# AccessPanelV3.net
KiCad netlist of a schematic drawn in EAGLE
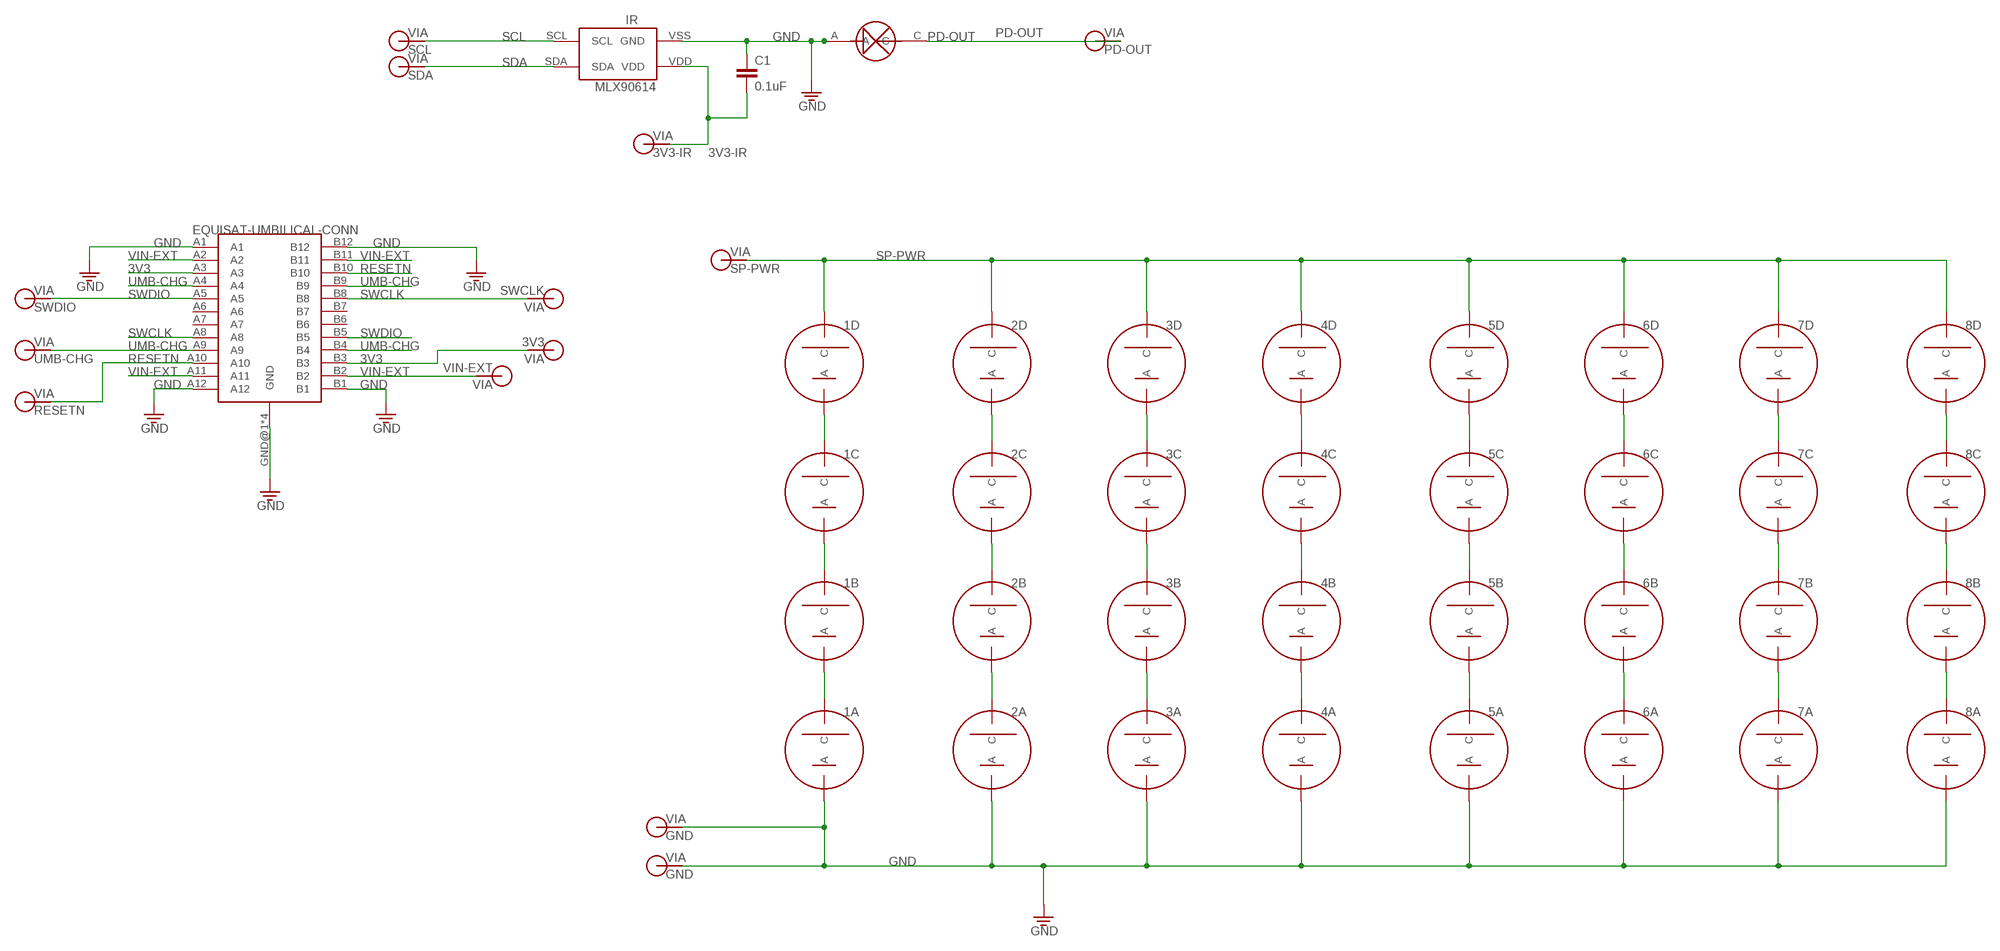
[diagram p0: schematic, sheet 1]

(export (version "E")
  (design (tool "Eeschema 10.0.6"))
  (components
    (comp (ref "1A")
      (value "SOLARCELLV3")
      (footprint "eagle-import:TRISOLX-V3")
      (libsource (lib "eagle-import") (part "SOLARCELLV3"))
    )
    (comp (ref "1B")
      (value "SOLARCELLV3")
      (footprint "eagle-import:TRISOLX-V3")
      (libsource (lib "eagle-import") (part "SOLARCELLV3"))
    )
    (comp (ref "1C")
      (value "SOLARCELLV3")
      (footprint "eagle-import:TRISOLX-V3")
      (libsource (lib "eagle-import") (part "SOLARCELLV3"))
    )
    (comp (ref "1D")
      (value "SOLARCELLV3")
      (footprint "eagle-import:TRISOLX-V3")
      (libsource (lib "eagle-import") (part "SOLARCELLV3"))
    )
    (comp (ref "2A")
      (value "SOLARCELLV3")
      (footprint "eagle-import:TRISOLX-V3")
      (libsource (lib "eagle-import") (part "SOLARCELLV3"))
    )
    (comp (ref "2B")
      (value "SOLARCELLV3")
      (footprint "eagle-import:TRISOLX-V3")
      (libsource (lib "eagle-import") (part "SOLARCELLV3"))
    )
    (comp (ref "2C")
      (value "SOLARCELLV3")
      (footprint "eagle-import:TRISOLX-V3")
      (libsource (lib "eagle-import") (part "SOLARCELLV3"))
    )
    (comp (ref "2D")
      (value "SOLARCELLV3")
      (footprint "eagle-import:TRISOLX-V3")
      (libsource (lib "eagle-import") (part "SOLARCELLV3"))
    )
    (comp (ref "3A")
      (value "SOLARCELLV3")
      (footprint "eagle-import:TRISOLX-V3")
      (libsource (lib "eagle-import") (part "SOLARCELLV3"))
    )
    (comp (ref "3B")
      (value "SOLARCELLV3")
      (footprint "eagle-import:TRISOLX-V3")
      (libsource (lib "eagle-import") (part "SOLARCELLV3"))
    )
    (comp (ref "3C")
      (value "SOLARCELLV3")
      (footprint "eagle-import:TRISOLX-V3")
      (libsource (lib "eagle-import") (part "SOLARCELLV3"))
    )
    (comp (ref "3D")
      (value "SOLARCELLV3")
      (footprint "eagle-import:TRISOLX-V3")
      (libsource (lib "eagle-import") (part "SOLARCELLV3"))
    )
    (comp (ref "4A")
      (value "SOLARCELLV3")
      (footprint "eagle-import:TRISOLX-V3")
      (libsource (lib "eagle-import") (part "SOLARCELLV3"))
    )
    (comp (ref "4B")
      (value "SOLARCELLV3")
      (footprint "eagle-import:TRISOLX-V3")
      (libsource (lib "eagle-import") (part "SOLARCELLV3"))
    )
    (comp (ref "4C")
      (value "SOLARCELLV3")
      (footprint "eagle-import:TRISOLX-V3")
      (libsource (lib "eagle-import") (part "SOLARCELLV3"))
    )
    (comp (ref "4D")
      (value "SOLARCELLV3")
      (footprint "eagle-import:TRISOLX-V3")
      (libsource (lib "eagle-import") (part "SOLARCELLV3"))
    )
    (comp (ref "5A")
      (value "SOLARCELLV3")
      (footprint "eagle-import:TRISOLX-V3")
      (libsource (lib "eagle-import") (part "SOLARCELLV3"))
    )
    (comp (ref "5B")
      (value "SOLARCELLV3")
      (footprint "eagle-import:TRISOLX-V3")
      (libsource (lib "eagle-import") (part "SOLARCELLV3"))
    )
    (comp (ref "5C")
      (value "SOLARCELLV3")
      (footprint "eagle-import:TRISOLX-V3")
      (libsource (lib "eagle-import") (part "SOLARCELLV3"))
    )
    (comp (ref "5D")
      (value "SOLARCELLV3")
      (footprint "eagle-import:TRISOLX-V3")
      (libsource (lib "eagle-import") (part "SOLARCELLV3"))
    )
    (comp (ref "6A")
      (value "SOLARCELLV3")
      (footprint "eagle-import:TRISOLX-V3")
      (libsource (lib "eagle-import") (part "SOLARCELLV3"))
    )
    (comp (ref "6B")
      (value "SOLARCELLV3")
      (footprint "eagle-import:TRISOLX-V3")
      (libsource (lib "eagle-import") (part "SOLARCELLV3"))
    )
    (comp (ref "6C")
      (value "SOLARCELLV3")
      (footprint "eagle-import:TRISOLX-V3")
      (libsource (lib "eagle-import") (part "SOLARCELLV3"))
    )
    (comp (ref "6D")
      (value "SOLARCELLV3")
      (footprint "eagle-import:TRISOLX-V3")
      (libsource (lib "eagle-import") (part "SOLARCELLV3"))
    )
    (comp (ref "7A")
      (value "SOLARCELLV3")
      (footprint "eagle-import:TRISOLX-V3")
      (libsource (lib "eagle-import") (part "SOLARCELLV3"))
    )
    (comp (ref "7B")
      (value "SOLARCELLV3")
      (footprint "eagle-import:TRISOLX-V3")
      (libsource (lib "eagle-import") (part "SOLARCELLV3"))
    )
    (comp (ref "7C")
      (value "SOLARCELLV3")
      (footprint "eagle-import:TRISOLX-V3")
      (libsource (lib "eagle-import") (part "SOLARCELLV3"))
    )
    (comp (ref "7D")
      (value "SOLARCELLV3")
      (footprint "eagle-import:TRISOLX-V3")
      (libsource (lib "eagle-import") (part "SOLARCELLV3"))
    )
    (comp (ref "8A")
      (value "SOLARCELLV3")
      (footprint "eagle-import:TRISOLX-V3")
      (libsource (lib "eagle-import") (part "SOLARCELLV3"))
    )
    (comp (ref "8B")
      (value "SOLARCELLV3")
      (footprint "eagle-import:TRISOLX-V3")
      (libsource (lib "eagle-import") (part "SOLARCELLV3"))
    )
    (comp (ref "8C")
      (value "SOLARCELLV3")
      (footprint "eagle-import:TRISOLX-V3")
      (libsource (lib "eagle-import") (part "SOLARCELLV3"))
    )
    (comp (ref "8D")
      (value "SOLARCELLV3")
      (footprint "eagle-import:TRISOLX-V3")
      (libsource (lib "eagle-import") (part "SOLARCELLV3"))
    )
    (comp (ref "C1")
      (value "0.1uF")
      (footprint "eagle-import:0805")
      (libsource (lib "eagle-import") (part "CAP0805"))
    )
    (comp (ref "IR")
      (value "MXL90614")
      (footprint "eagle-import:MXL90620")
      (libsource (lib "eagle-import") (part "MXL90614"))
    )
    (comp (ref "PD")
      (value "TEMD6200")
      (footprint "eagle-import:TEMD6200")
      (libsource (lib "eagle-import") (part "TEMD6200"))
    )
    (comp (ref "SCL")
      (value "SCL")
      (footprint "eagle-import:VIA-60MIL")
      (libsource (lib "eagle-import") (part "VIA-60MIL"))
    )
    (comp (ref "SDA")
      (value "SDA")
      (footprint "eagle-import:VIA-60MIL")
      (libsource (lib "eagle-import") (part "VIA-60MIL"))
    )
    (comp (ref "UMB-CONN")
      (value "EQUISAT-UMBILICAL-CONN")
      (footprint "eagle-import:USB-C-RCPT-SMT")
      (libsource (lib "eagle-import") (part "EQUISAT-UMBILICAL-CONN"))
    )
    (comp (ref "V1")
      (value "SP-PWR")
      (footprint "eagle-import:VIA-60MIL")
      (libsource (lib "eagle-import") (part "VIA-60MIL"))
    )
    (comp (ref "V2")
      (value "GND")
      (footprint "eagle-import:VIA-60MIL")
      (libsource (lib "eagle-import") (part "VIA-60MIL"))
    )
    (comp (ref "V3")
      (value "3V3-IR")
      (footprint "eagle-import:VIA-60MIL")
      (libsource (lib "eagle-import") (part "VIA-60MIL"))
    )
    (comp (ref "V4")
      (value "GND")
      (footprint "eagle-import:VIA-60MIL")
      (libsource (lib "eagle-import") (part "VIA-60MIL"))
    )
    (comp (ref "V5")
      (value "UMB-CHG")
      (footprint "eagle-import:VIA-60MIL")
      (libsource (lib "eagle-import") (part "VIA-60MIL"))
    )
    (comp (ref "V6")
      (value "PD-OUT")
      (footprint "eagle-import:VIA-60MIL")
      (libsource (lib "eagle-import") (part "VIA-60MIL"))
    )
    (comp (ref "V7")
      (value "VIN-EXT")
      (footprint "eagle-import:VIA-60MIL")
      (libsource (lib "eagle-import") (part "VIA-60MIL"))
    )
    (comp (ref "V8")
      (value "RESETN")
      (footprint "eagle-import:VIA-60MIL")
      (libsource (lib "eagle-import") (part "VIA-60MIL"))
    )
    (comp (ref "V9")
      (value "3V3")
      (footprint "eagle-import:VIA-60MIL")
      (libsource (lib "eagle-import") (part "VIA-60MIL"))
    )
    (comp (ref "V10")
      (value "SWCLK")
      (footprint "eagle-import:VIA-60MIL")
      (libsource (lib "eagle-import") (part "VIA-60MIL"))
    )
    (comp (ref "V11")
      (value "SWDIO")
      (footprint "eagle-import:VIA-60MIL")
      (libsource (lib "eagle-import") (part "VIA-60MIL"))
    )
  )
  (nets
    (net (code "1") (name "/3V3") (class "Default")
      (node (ref "UMB-CONN") (pin "A3") (pinfunction "A3_A3") (pintype "bidirectional"))
      (node (ref "UMB-CONN") (pin "B3") (pinfunction "B3_B3") (pintype "bidirectional"))
      (node (ref "V9") (pin "P$1") (pinfunction "P$1_P$1") (pintype "bidirectional"))
    )
    (net (code "2") (name "/3V3-IR") (class "Default")
      (node (ref "C1") (pin "2") (pinfunction "2_2") (pintype "passive"))
      (node (ref "IR") (pin "VDD") (pinfunction "VDD_VDD") (pintype "bidirectional"))
      (node (ref "V3") (pin "P$1") (pinfunction "P$1_P$1") (pintype "bidirectional"))
    )
    (net (code "3") (name "/PD-OUT") (class "Default")
      (node (ref "PD") (pin "C") (pinfunction "C_C") (pintype "bidirectional"))
      (node (ref "V6") (pin "P$1") (pinfunction "P$1_P$1") (pintype "bidirectional"))
    )
    (net (code "4") (name "/RESETN") (class "Default")
      (node (ref "UMB-CONN") (pin "A10") (pinfunction "A10_A10") (pintype "bidirectional"))
      (node (ref "UMB-CONN") (pin "B10") (pinfunction "B10_B10") (pintype "bidirectional"))
      (node (ref "V8") (pin "P$1") (pinfunction "P$1_P$1") (pintype "bidirectional"))
    )
    (net (code "5") (name "/SCL") (class "Default")
      (node (ref "IR") (pin "SCL") (pinfunction "SCL_SCL") (pintype "bidirectional"))
      (node (ref "SCL") (pin "P$1") (pinfunction "P$1_P$1") (pintype "bidirectional"))
    )
    (net (code "6") (name "/SDA") (class "Default")
      (node (ref "IR") (pin "SDA") (pinfunction "SDA_SDA") (pintype "bidirectional"))
      (node (ref "SDA") (pin "P$1") (pinfunction "P$1_P$1") (pintype "bidirectional"))
    )
    (net (code "7") (name "/SP-PWR") (class "Default")
      (node (ref "1D") (pin "CATHODE") (pinfunction "C_CATHODE") (pintype "bidirectional"))
      (node (ref "2D") (pin "CATHODE") (pinfunction "C_CATHODE") (pintype "bidirectional"))
      (node (ref "3D") (pin "CATHODE") (pinfunction "C_CATHODE") (pintype "bidirectional"))
      (node (ref "4D") (pin "CATHODE") (pinfunction "C_CATHODE") (pintype "bidirectional"))
      (node (ref "5D") (pin "CATHODE") (pinfunction "C_CATHODE") (pintype "bidirectional"))
      (node (ref "6D") (pin "CATHODE") (pinfunction "C_CATHODE") (pintype "bidirectional"))
      (node (ref "7D") (pin "CATHODE") (pinfunction "C_CATHODE") (pintype "bidirectional"))
      (node (ref "8D") (pin "CATHODE") (pinfunction "C_CATHODE") (pintype "bidirectional"))
      (node (ref "V1") (pin "P$1") (pinfunction "P$1_P$1") (pintype "bidirectional"))
    )
    (net (code "8") (name "/SWCLK") (class "Default")
      (node (ref "UMB-CONN") (pin "A8") (pinfunction "A8_A8") (pintype "bidirectional"))
      (node (ref "UMB-CONN") (pin "B8") (pinfunction "B8_B8") (pintype "bidirectional"))
      (node (ref "V10") (pin "P$1") (pinfunction "P$1_P$1") (pintype "bidirectional"))
    )
    (net (code "9") (name "/SWDIO") (class "Default")
      (node (ref "UMB-CONN") (pin "A5") (pinfunction "A5_A5") (pintype "bidirectional"))
      (node (ref "UMB-CONN") (pin "B5") (pinfunction "B5_B5") (pintype "bidirectional"))
      (node (ref "V11") (pin "P$1") (pinfunction "P$1_P$1") (pintype "bidirectional"))
    )
    (net (code "10") (name "/UMB-CHG") (class "Default")
      (node (ref "UMB-CONN") (pin "A4") (pinfunction "A4_A4") (pintype "bidirectional"))
      (node (ref "UMB-CONN") (pin "A9") (pinfunction "A9_A9") (pintype "bidirectional"))
      (node (ref "UMB-CONN") (pin "B4") (pinfunction "B4_B4") (pintype "bidirectional"))
      (node (ref "UMB-CONN") (pin "B9") (pinfunction "B9_B9") (pintype "bidirectional"))
      (node (ref "V5") (pin "P$1") (pinfunction "P$1_P$1") (pintype "bidirectional"))
    )
    (net (code "11") (name "/VIN-EXT") (class "Default")
      (node (ref "UMB-CONN") (pin "A11") (pinfunction "A11_A11") (pintype "bidirectional"))
      (node (ref "UMB-CONN") (pin "A2") (pinfunction "A2_A2") (pintype "bidirectional"))
      (node (ref "UMB-CONN") (pin "B11") (pinfunction "B11_B11") (pintype "bidirectional"))
      (node (ref "UMB-CONN") (pin "B2") (pinfunction "B2_B2") (pintype "bidirectional"))
      (node (ref "V7") (pin "P$1") (pinfunction "P$1_P$1") (pintype "bidirectional"))
    )
    (net (code "12") (name "GND") (class "Default")
      (node (ref "1A") (pin "ANODE") (pinfunction "A_ANODE") (pintype "bidirectional"))
      (node (ref "2A") (pin "ANODE") (pinfunction "A_ANODE") (pintype "bidirectional"))
      (node (ref "3A") (pin "ANODE") (pinfunction "A_ANODE") (pintype "bidirectional"))
      (node (ref "4A") (pin "ANODE") (pinfunction "A_ANODE") (pintype "bidirectional"))
      (node (ref "5A") (pin "ANODE") (pinfunction "A_ANODE") (pintype "bidirectional"))
      (node (ref "6A") (pin "ANODE") (pinfunction "A_ANODE") (pintype "bidirectional"))
      (node (ref "7A") (pin "ANODE") (pinfunction "A_ANODE") (pintype "bidirectional"))
      (node (ref "8A") (pin "ANODE") (pinfunction "A_ANODE") (pintype "bidirectional"))
      (node (ref "C1") (pin "1") (pinfunction "1_1") (pintype "passive"))
      (node (ref "IR") (pin "VSS") (pinfunction "GND_VSS") (pintype "bidirectional"))
      (node (ref "PD") (pin "A") (pinfunction "A_A") (pintype "bidirectional"))
      (node (ref "UMB-CONN") (pin "A1") (pinfunction "A1_A1") (pintype "bidirectional"))
      (node (ref "UMB-CONN") (pin "A12") (pinfunction "A12_A12") (pintype "bidirectional"))
      (node (ref "UMB-CONN") (pin "B1") (pinfunction "B1_B1") (pintype "bidirectional"))
      (node (ref "UMB-CONN") (pin "B12") (pinfunction "B12_B12") (pintype "bidirectional"))
      (node (ref "UMB-CONN") (pin "GND@1") (pinfunction "GND_GND@1") (pintype "bidirectional"))
      (node (ref "UMB-CONN") (pin "GND@2") (pinfunction "GND_GND@2") (pintype "bidirectional"))
      (node (ref "UMB-CONN") (pin "GND@3") (pinfunction "GND_GND@3") (pintype "bidirectional"))
      (node (ref "UMB-CONN") (pin "GND@4") (pinfunction "GND_GND@4") (pintype "bidirectional"))
      (node (ref "V2") (pin "P$1") (pinfunction "P$1_P$1") (pintype "bidirectional"))
      (node (ref "V4") (pin "P$1") (pinfunction "P$1_P$1") (pintype "bidirectional"))
    )
    (net (code "13") (name "Net-(1A-C)") (class "Default")
      (node (ref "1A") (pin "CATHODE") (pinfunction "C_CATHODE") (pintype "bidirectional"))
      (node (ref "1B") (pin "ANODE") (pinfunction "A_ANODE") (pintype "bidirectional"))
    )
    (net (code "14") (name "Net-(1B-C)") (class "Default")
      (node (ref "1B") (pin "CATHODE") (pinfunction "C_CATHODE") (pintype "bidirectional"))
      (node (ref "1C") (pin "ANODE") (pinfunction "A_ANODE") (pintype "bidirectional"))
    )
    (net (code "15") (name "Net-(1C-C)") (class "Default")
      (node (ref "1C") (pin "CATHODE") (pinfunction "C_CATHODE") (pintype "bidirectional"))
      (node (ref "1D") (pin "ANODE") (pinfunction "A_ANODE") (pintype "bidirectional"))
    )
    (net (code "16") (name "Net-(2A-C)") (class "Default")
      (node (ref "2A") (pin "CATHODE") (pinfunction "C_CATHODE") (pintype "bidirectional"))
      (node (ref "2B") (pin "ANODE") (pinfunction "A_ANODE") (pintype "bidirectional"))
    )
    (net (code "17") (name "Net-(2B-C)") (class "Default")
      (node (ref "2B") (pin "CATHODE") (pinfunction "C_CATHODE") (pintype "bidirectional"))
      (node (ref "2C") (pin "ANODE") (pinfunction "A_ANODE") (pintype "bidirectional"))
    )
    (net (code "18") (name "Net-(2C-C)") (class "Default")
      (node (ref "2C") (pin "CATHODE") (pinfunction "C_CATHODE") (pintype "bidirectional"))
      (node (ref "2D") (pin "ANODE") (pinfunction "A_ANODE") (pintype "bidirectional"))
    )
    (net (code "19") (name "Net-(3A-C)") (class "Default")
      (node (ref "3A") (pin "CATHODE") (pinfunction "C_CATHODE") (pintype "bidirectional"))
      (node (ref "3B") (pin "ANODE") (pinfunction "A_ANODE") (pintype "bidirectional"))
    )
    (net (code "20") (name "Net-(3B-C)") (class "Default")
      (node (ref "3B") (pin "CATHODE") (pinfunction "C_CATHODE") (pintype "bidirectional"))
      (node (ref "3C") (pin "ANODE") (pinfunction "A_ANODE") (pintype "bidirectional"))
    )
    (net (code "21") (name "Net-(3C-C)") (class "Default")
      (node (ref "3C") (pin "CATHODE") (pinfunction "C_CATHODE") (pintype "bidirectional"))
      (node (ref "3D") (pin "ANODE") (pinfunction "A_ANODE") (pintype "bidirectional"))
    )
    (net (code "22") (name "Net-(4A-C)") (class "Default")
      (node (ref "4A") (pin "CATHODE") (pinfunction "C_CATHODE") (pintype "bidirectional"))
      (node (ref "4B") (pin "ANODE") (pinfunction "A_ANODE") (pintype "bidirectional"))
    )
    (net (code "23") (name "Net-(4B-C)") (class "Default")
      (node (ref "4B") (pin "CATHODE") (pinfunction "C_CATHODE") (pintype "bidirectional"))
      (node (ref "4C") (pin "ANODE") (pinfunction "A_ANODE") (pintype "bidirectional"))
    )
    (net (code "24") (name "Net-(4C-C)") (class "Default")
      (node (ref "4C") (pin "CATHODE") (pinfunction "C_CATHODE") (pintype "bidirectional"))
      (node (ref "4D") (pin "ANODE") (pinfunction "A_ANODE") (pintype "bidirectional"))
    )
    (net (code "25") (name "Net-(5A-C)") (class "Default")
      (node (ref "5A") (pin "CATHODE") (pinfunction "C_CATHODE") (pintype "bidirectional"))
      (node (ref "5B") (pin "ANODE") (pinfunction "A_ANODE") (pintype "bidirectional"))
    )
    (net (code "26") (name "Net-(5B-C)") (class "Default")
      (node (ref "5B") (pin "CATHODE") (pinfunction "C_CATHODE") (pintype "bidirectional"))
      (node (ref "5C") (pin "ANODE") (pinfunction "A_ANODE") (pintype "bidirectional"))
    )
    (net (code "27") (name "Net-(5C-C)") (class "Default")
      (node (ref "5C") (pin "CATHODE") (pinfunction "C_CATHODE") (pintype "bidirectional"))
      (node (ref "5D") (pin "ANODE") (pinfunction "A_ANODE") (pintype "bidirectional"))
    )
    (net (code "28") (name "Net-(6A-C)") (class "Default")
      (node (ref "6A") (pin "CATHODE") (pinfunction "C_CATHODE") (pintype "bidirectional"))
      (node (ref "6B") (pin "ANODE") (pinfunction "A_ANODE") (pintype "bidirectional"))
    )
    (net (code "29") (name "Net-(6B-C)") (class "Default")
      (node (ref "6B") (pin "CATHODE") (pinfunction "C_CATHODE") (pintype "bidirectional"))
      (node (ref "6C") (pin "ANODE") (pinfunction "A_ANODE") (pintype "bidirectional"))
    )
    (net (code "30") (name "Net-(6C-C)") (class "Default")
      (node (ref "6C") (pin "CATHODE") (pinfunction "C_CATHODE") (pintype "bidirectional"))
      (node (ref "6D") (pin "ANODE") (pinfunction "A_ANODE") (pintype "bidirectional"))
    )
    (net (code "31") (name "Net-(7A-C)") (class "Default")
      (node (ref "7A") (pin "CATHODE") (pinfunction "C_CATHODE") (pintype "bidirectional"))
      (node (ref "7B") (pin "ANODE") (pinfunction "A_ANODE") (pintype "bidirectional"))
    )
    (net (code "32") (name "Net-(7B-C)") (class "Default")
      (node (ref "7B") (pin "CATHODE") (pinfunction "C_CATHODE") (pintype "bidirectional"))
      (node (ref "7C") (pin "ANODE") (pinfunction "A_ANODE") (pintype "bidirectional"))
    )
    (net (code "33") (name "Net-(7C-C)") (class "Default")
      (node (ref "7C") (pin "CATHODE") (pinfunction "C_CATHODE") (pintype "bidirectional"))
      (node (ref "7D") (pin "ANODE") (pinfunction "A_ANODE") (pintype "bidirectional"))
    )
    (net (code "34") (name "Net-(8A-C)") (class "Default")
      (node (ref "8A") (pin "CATHODE") (pinfunction "C_CATHODE") (pintype "bidirectional"))
      (node (ref "8B") (pin "ANODE") (pinfunction "A_ANODE") (pintype "bidirectional"))
    )
    (net (code "35") (name "Net-(8B-C)") (class "Default")
      (node (ref "8B") (pin "CATHODE") (pinfunction "C_CATHODE") (pintype "bidirectional"))
      (node (ref "8C") (pin "ANODE") (pinfunction "A_ANODE") (pintype "bidirectional"))
    )
    (net (code "36") (name "Net-(8C-C)") (class "Default")
      (node (ref "8C") (pin "CATHODE") (pinfunction "C_CATHODE") (pintype "bidirectional"))
      (node (ref "8D") (pin "ANODE") (pinfunction "A_ANODE") (pintype "bidirectional"))
    )
    (net (code "37") (name "unconnected-(UMB-CONN-PadA6)") (class "Default")
      (node (ref "UMB-CONN") (pin "A6") (pinfunction "A6_A6") (pintype "bidirectional"))
    )
    (net (code "38") (name "unconnected-(UMB-CONN-PadA7)") (class "Default")
      (node (ref "UMB-CONN") (pin "A7") (pinfunction "A7_A7") (pintype "bidirectional"))
    )
    (net (code "39") (name "unconnected-(UMB-CONN-PadB6)") (class "Default")
      (node (ref "UMB-CONN") (pin "B6") (pinfunction "B6_B6") (pintype "bidirectional"))
    )
    (net (code "40") (name "unconnected-(UMB-CONN-PadB7)") (class "Default")
      (node (ref "UMB-CONN") (pin "B7") (pinfunction "B7_B7") (pintype "bidirectional"))
    )
  )
)
